# 09_Misc.net
KiCad netlist of a schematic drawn in Altium Designer
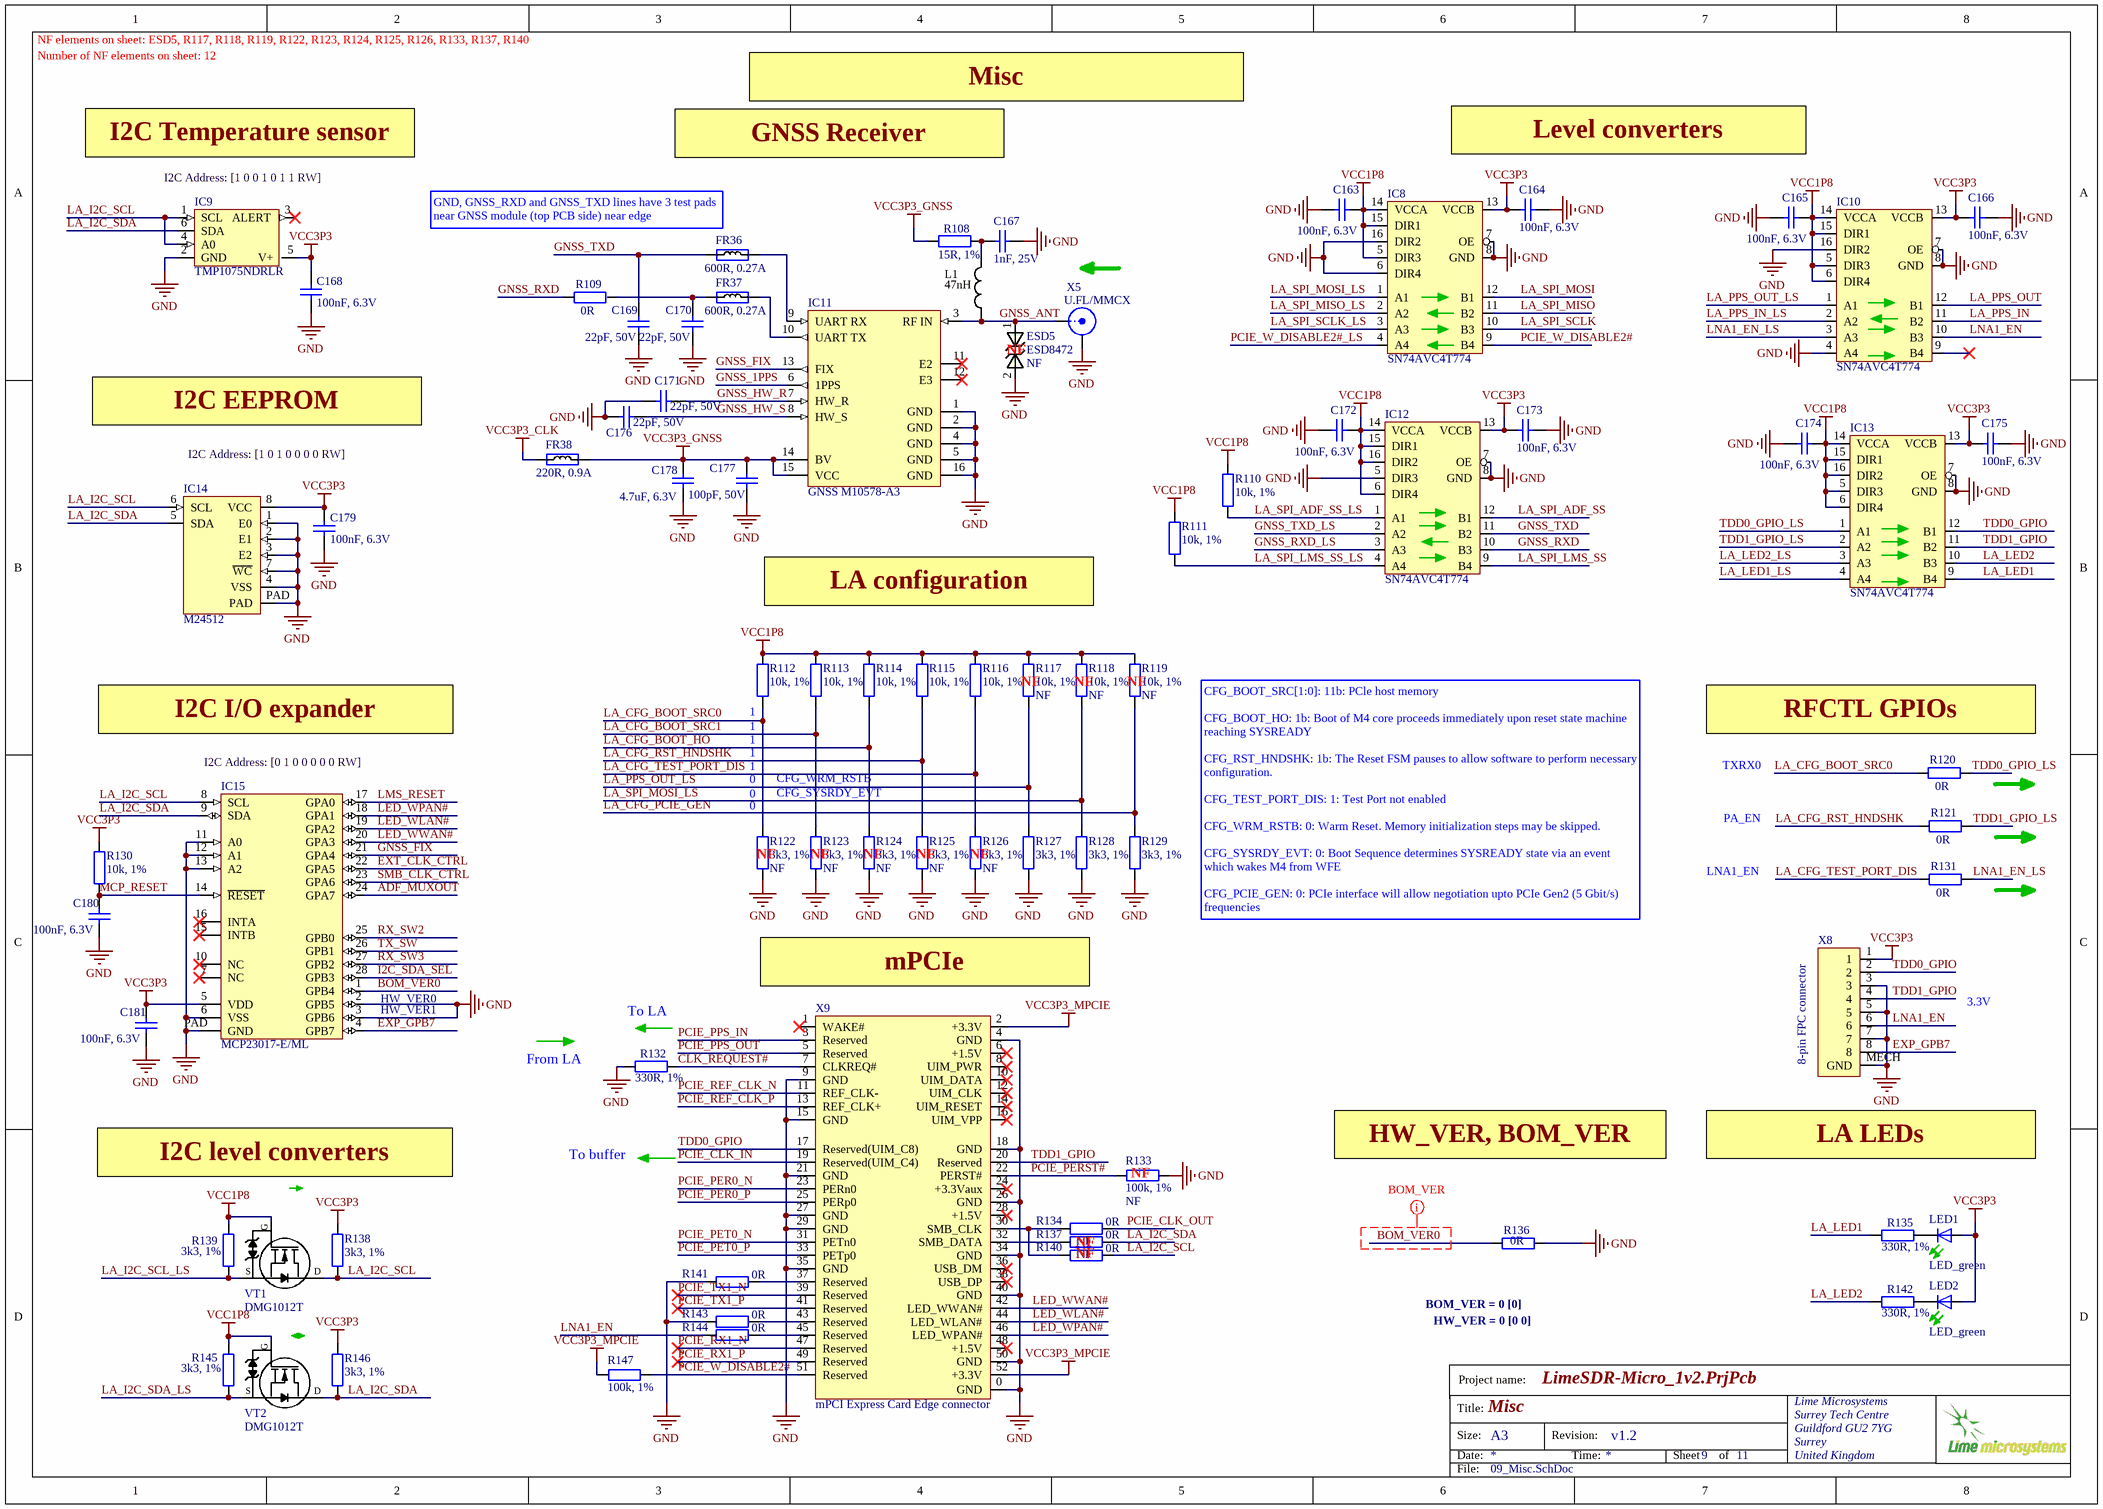
[diagram p0: 09_Misc.SchDoc]

(export (version "E")
  (design (tool "Eeschema 10.0.6"))
  (components
    (comp (ref "C163")
      (value "100nF, 6.3V")
      (footprint "CAP0201")
      (fields (field (name "MANUFACTURER") "Samsung") (field (name "TOLERANCE") "20%"))
      (libsource (lib "LimeMicroAltiumLib_schLib") (part "Cap_0402"))
    )
    (comp (ref "C164")
      (value "100nF, 6.3V")
      (footprint "CAP0201")
      (fields (field (name "MANUFACTURER") "Samsung") (field (name "TOLERANCE") "20%"))
      (libsource (lib "LimeMicroAltiumLib_schLib") (part "Cap_0402"))
    )
    (comp (ref "C165")
      (value "100nF, 6.3V")
      (footprint "CAP0201")
      (fields (field (name "MANUFACTURER") "Samsung") (field (name "TOLERANCE") "20%"))
      (libsource (lib "LimeMicroAltiumLib_schLib") (part "Cap_0402"))
    )
    (comp (ref "C166")
      (value "100nF, 6.3V")
      (footprint "CAP0201")
      (fields (field (name "MANUFACTURER") "Samsung") (field (name "TOLERANCE") "20%"))
      (libsource (lib "LimeMicroAltiumLib_schLib") (part "Cap_0402"))
    )
    (comp (ref "C167")
      (value "1nF, 25V")
      (footprint "CAP0201")
      (fields (field (name "TOLERANCE") "±10%") (field (name "MANUFACTURER") "TDK Corporation"))
      (libsource (lib "LimeMicroAltiumLib_schLib") (part "Cap_0402"))
    )
    (comp (ref "C168")
      (value "100nF, 6.3V")
      (footprint "CAP0201")
      (fields (field (name "MANUFACTURER") "Samsung") (field (name "TOLERANCE") "20%"))
      (libsource (lib "LimeMicroAltiumLib_schLib") (part "Cap_0402"))
    )
    (comp (ref "C169")
      (value "22pF, 50V")
      (footprint "CAP0201")
      (fields
        (field (name "MANUFACTURER") "Murata")
        (field (name "TOLERANCE") "5%")
        (field (name "VOLTAGE") "50V")
      )
      (libsource (lib "LimeMicroAltiumLib_schLib") (part "Cap_0402"))
    )
    (comp (ref "C170")
      (value "22pF, 50V")
      (footprint "CAP0201")
      (fields
        (field (name "MANUFACTURER") "Murata")
        (field (name "TOLERANCE") "5%")
        (field (name "VOLTAGE") "50V")
      )
      (libsource (lib "LimeMicroAltiumLib_schLib") (part "Cap_0402"))
    )
    (comp (ref "C171")
      (value "22pF, 50V")
      (footprint "CAP0201")
      (fields
        (field (name "MANUFACTURER") "Murata")
        (field (name "TOLERANCE") "5%")
        (field (name "VOLTAGE") "50V")
      )
      (libsource (lib "LimeMicroAltiumLib_schLib") (part "Cap_0402"))
    )
    (comp (ref "C172")
      (value "100nF, 6.3V")
      (footprint "CAP0201")
      (fields (field (name "MANUFACTURER") "Samsung") (field (name "TOLERANCE") "20%"))
      (libsource (lib "LimeMicroAltiumLib_schLib") (part "Cap_0402"))
    )
    (comp (ref "C173")
      (value "100nF, 6.3V")
      (footprint "CAP0201")
      (fields (field (name "MANUFACTURER") "Samsung") (field (name "TOLERANCE") "20%"))
      (libsource (lib "LimeMicroAltiumLib_schLib") (part "Cap_0402"))
    )
    (comp (ref "C174")
      (value "100nF, 6.3V")
      (footprint "CAP0201")
      (fields (field (name "MANUFACTURER") "Samsung") (field (name "TOLERANCE") "20%"))
      (libsource (lib "LimeMicroAltiumLib_schLib") (part "Cap_0402"))
    )
    (comp (ref "C175")
      (value "100nF, 6.3V")
      (footprint "CAP0201")
      (fields (field (name "MANUFACTURER") "Samsung") (field (name "TOLERANCE") "20%"))
      (libsource (lib "LimeMicroAltiumLib_schLib") (part "Cap_0402"))
    )
    (comp (ref "C176")
      (value "22pF, 50V")
      (footprint "CAP0201")
      (fields
        (field (name "MANUFACTURER") "Murata")
        (field (name "TOLERANCE") "5%")
        (field (name "VOLTAGE") "50V")
      )
      (libsource (lib "LimeMicroAltiumLib_schLib") (part "Cap_0402"))
    )
    (comp (ref "C177")
      (value "100pF, 50V")
      (footprint "CAP0201")
      (fields
        (field (name "MANUFACTURER") "TDK")
        (field (name "TOLERANCE") "5%")
        (field (name "VOLTAGE") "50V")
      )
      (libsource (lib "LimeMicroAltiumLib_schLib") (part "Cap_0402"))
    )
    (comp (ref "C178")
      (value "4.7uF, 6.3V")
      (footprint "CAP0402")
      (fields
        (field (name "MANUFACTURER") "Murata Electronics North America")
        (field (name "TOLERANCE") "±20%")
      )
      (libsource (lib "LimeMicroAltiumLib_schLib") (part "Cap_0402"))
    )
    (comp (ref "C179")
      (value "100nF, 6.3V")
      (footprint "CAP0201")
      (fields (field (name "MANUFACTURER") "Samsung") (field (name "TOLERANCE") "20%"))
      (libsource (lib "LimeMicroAltiumLib_schLib") (part "Cap_0402"))
    )
    (comp (ref "C180")
      (value "100nF, 6.3V")
      (footprint "CAP0201")
      (fields (field (name "MANUFACTURER") "Samsung") (field (name "TOLERANCE") "20%"))
      (libsource (lib "LimeMicroAltiumLib_schLib") (part "Cap_0402"))
    )
    (comp (ref "C181")
      (value "100nF, 6.3V")
      (footprint "CAP0201")
      (fields (field (name "MANUFACTURER") "Samsung") (field (name "TOLERANCE") "20%"))
      (libsource (lib "LimeMicroAltiumLib_schLib") (part "Cap_0402"))
    )
    (comp (ref "ESD5")
      (value "ESD8472")
      (footprint "ESD8472_X3DFN2")
      (fields (field (name "MANUFACTURER") "ON Semiconductor") (field (name "ASSEMBLY INFO") "NF"))
      (libsource (lib "LimeMicroAltiumLib_schLib") (part "ESD8472"))
    )
    (comp (ref "FR36")
      (value "600R, 0.27A")
      (footprint "RES0201")
      (fields (field (name "MANUFACTURER") "Taiyo Yuden"))
      (libsource (lib "LimeMicroAltiumLib_schLib") (part "Ferrite"))
    )
    (comp (ref "FR37")
      (value "600R, 0.27A")
      (footprint "RES0201")
      (fields (field (name "MANUFACTURER") "Taiyo Yuden"))
      (libsource (lib "LimeMicroAltiumLib_schLib") (part "Ferrite"))
    )
    (comp (ref "FR38")
      (value "220R, 0.9A")
      (footprint "RES0402")
      (fields (field (name "MANUFACTURER") "TDK Corporation"))
      (libsource (lib "LimeFPGAboard_schLib") (part "Ferrite"))
    )
    (comp (ref "IC8")
      (value "SN74AVC4T774")
      (footprint "SN74AVC4T774_v1")
      (fields (field (name "MANUFACTURER") "Texas Instruments"))
      (libsource (lib "LimeMicroAltiumLib") (part "SN74AVC4T774"))
    )
    (comp (ref "IC9")
      (value "TMP1075NDRLR")
      (footprint "TMP1075NDRLR_temperature_sensor_SOT563")
      (fields (field (name "MANUFACTURER") "Texas Instruments"))
      (libsource (lib "LimeMicroAltiumLib_schLib_r04") (part "TMP1075NDRLR_temperature_sensor"))
    )
    (comp (ref "IC10")
      (value "SN74AVC4T774")
      (footprint "SN74AVC4T774_v1")
      (fields (field (name "MANUFACTURER") "Texas Instruments"))
      (libsource (lib "LimeMicroAltiumLib") (part "SN74AVC4T774"))
    )
    (comp (ref "IC11")
      (value "GNSS M10578-A3")
      (footprint "M10578-A3_v2")
      (fields (field (name "MANUFACTURER") "Antenova"))
      (libsource (lib "LimeMicroAltiumLib_schLib_r04") (part "M10578-A3_GPS_GNSS"))
    )
    (comp (ref "IC12")
      (value "SN74AVC4T774")
      (footprint "SN74AVC4T774_v1")
      (fields (field (name "MANUFACTURER") "Texas Instruments"))
      (libsource (lib "LimeMicroAltiumLib") (part "SN74AVC4T774"))
    )
    (comp (ref "IC13")
      (value "SN74AVC4T774")
      (footprint "SN74AVC4T774_v1")
      (fields (field (name "MANUFACTURER") "Texas Instruments"))
      (libsource (lib "LimeMicroAltiumLib") (part "SN74AVC4T774"))
    )
    (comp (ref "IC14")
      (value "M24512")
      (footprint "M24128-DFMC6TG")
      (fields (field (name "MANUFACTURER") "STMicroelectronics"))
      (libsource (lib "LimeMicroAltiumLib_schLib") (part "M24128-DFMC6TG"))
    )
    (comp (ref "IC15")
      (value "MCP23017-E/ML")
      (footprint "MCP23017-E/ML_QFN28")
      (fields (field (name "MANUFACTURER") "Microchip"))
      (libsource (lib "LimeMicroAltiumLib") (part "MCP23017-E/ML_I2C_expander"))
    )
    (comp (ref "L1")
      (value "47nH")
      (footprint "RES0402")
      (fields
        (field (name "MANUFACTURER") "COILCRAFT")
        (field (name "MANUFACTURER PART NUMBER") "0402HP-47NXJLU")
      )
      (libsource (lib "LimeMicroAltiumLib_schLib") (part "Inductor_0603"))
    )
    (comp (ref "LED1")
      (value "LED_green")
      (footprint "LED0201")
      (fields (field (name "MANUFACTURER") "Kingbright"))
      (libsource (lib "LimeFPGAboard_schLib") (part "LED_green"))
    )
    (comp (ref "LED2")
      (value "LED_green")
      (footprint "LED0201")
      (fields (field (name "MANUFACTURER") "Kingbright"))
      (libsource (lib "LimeFPGAboard_schLib") (part "LED_green"))
    )
    (comp (ref "R108")
      (value "15R, 1%")
      (footprint "RES0201")
      (fields (field (name "MANUFACTURER") "Yageo") (field (name "TOLERANCE") "1%"))
      (libsource (lib "LimeFPGAboard_schLib") (part "Res_0402"))
    )
    (comp (ref "R109")
      (value "0R")
      (footprint "RES0201")
      (fields (field (name "MANUFACTURER") "Yageo") (field (name "TOLERANCE") "5%"))
      (libsource (lib "LimeFPGAboard_schLib") (part "Res_0402"))
    )
    (comp (ref "R110")
      (value "10k, 1%")
      (footprint "RES0201")
      (fields (field (name "MANUFACTURER") "Yageo") (field (name "TOLERANCE") "1%"))
      (libsource (lib "LimeFPGAboard_schLib") (part "Res_0402"))
    )
    (comp (ref "R111")
      (value "10k, 1%")
      (footprint "RES0201")
      (fields (field (name "MANUFACTURER") "Yageo") (field (name "TOLERANCE") "1%"))
      (libsource (lib "LimeFPGAboard_schLib") (part "Res_0402"))
    )
    (comp (ref "R112")
      (value "10k, 1%")
      (footprint "RES0201")
      (fields (field (name "MANUFACTURER") "Yageo") (field (name "TOLERANCE") "1%"))
      (libsource (lib "LimeFPGAboard_schLib") (part "Res_0402"))
    )
    (comp (ref "R113")
      (value "10k, 1%")
      (footprint "RES0201")
      (fields (field (name "MANUFACTURER") "Yageo") (field (name "TOLERANCE") "1%"))
      (libsource (lib "LimeFPGAboard_schLib") (part "Res_0402"))
    )
    (comp (ref "R114")
      (value "10k, 1%")
      (footprint "RES0201")
      (fields (field (name "MANUFACTURER") "Yageo") (field (name "TOLERANCE") "1%"))
      (libsource (lib "LimeFPGAboard_schLib") (part "Res_0402"))
    )
    (comp (ref "R115")
      (value "10k, 1%")
      (footprint "RES0201")
      (fields (field (name "MANUFACTURER") "Yageo") (field (name "TOLERANCE") "1%"))
      (libsource (lib "LimeFPGAboard_schLib") (part "Res_0402"))
    )
    (comp (ref "R116")
      (value "10k, 1%")
      (footprint "RES0201")
      (fields (field (name "MANUFACTURER") "Yageo") (field (name "TOLERANCE") "1%"))
      (libsource (lib "LimeFPGAboard_schLib") (part "Res_0402"))
    )
    (comp (ref "R117")
      (value "10k, 1%")
      (footprint "RES0201")
      (fields
        (field (name "ASSEMBLY INFO") "NF")
        (field (name "MANUFACTURER") "Yageo")
        (field (name "TOLERANCE") "1%")
      )
      (libsource (lib "LimeFPGAboard_schLib") (part "Res_0402"))
    )
    (comp (ref "R118")
      (value "10k, 1%")
      (footprint "RES0201")
      (fields
        (field (name "ASSEMBLY INFO") "NF")
        (field (name "MANUFACTURER") "Yageo")
        (field (name "TOLERANCE") "1%")
      )
      (libsource (lib "LimeFPGAboard_schLib") (part "Res_0402"))
    )
    (comp (ref "R119")
      (value "10k, 1%")
      (footprint "RES0201")
      (fields
        (field (name "ASSEMBLY INFO") "NF")
        (field (name "MANUFACTURER") "Yageo")
        (field (name "TOLERANCE") "1%")
      )
      (libsource (lib "LimeFPGAboard_schLib") (part "Res_0402"))
    )
    (comp (ref "R120")
      (value "0R")
      (footprint "RES0201")
      (fields (field (name "MANUFACTURER") "Yageo") (field (name "TOLERANCE") "5%"))
      (libsource (lib "LimeFPGAboard_schLib") (part "Res_0402"))
    )
    (comp (ref "R121")
      (value "0R")
      (footprint "RES0201")
      (fields (field (name "MANUFACTURER") "Yageo") (field (name "TOLERANCE") "5%"))
      (libsource (lib "LimeFPGAboard_schLib") (part "Res_0402"))
    )
    (comp (ref "R122")
      (value "3k3, 1%")
      (footprint "RES0201")
      (fields
        (field (name "ASSEMBLY INFO") "NF")
        (field (name "MANUFACTURER") "Yageo")
        (field (name "TOLERANCE") "1%")
      )
      (libsource (lib "LimeFPGAboard_schLib") (part "Res_0402"))
    )
    (comp (ref "R123")
      (value "3k3, 1%")
      (footprint "RES0201")
      (fields
        (field (name "ASSEMBLY INFO") "NF")
        (field (name "MANUFACTURER") "Yageo")
        (field (name "TOLERANCE") "1%")
      )
      (libsource (lib "LimeFPGAboard_schLib") (part "Res_0402"))
    )
    (comp (ref "R124")
      (value "3k3, 1%")
      (footprint "RES0201")
      (fields
        (field (name "ASSEMBLY INFO") "NF")
        (field (name "MANUFACTURER") "Yageo")
        (field (name "TOLERANCE") "1%")
      )
      (libsource (lib "LimeFPGAboard_schLib") (part "Res_0402"))
    )
    (comp (ref "R125")
      (value "3k3, 1%")
      (footprint "RES0201")
      (fields
        (field (name "ASSEMBLY INFO") "NF")
        (field (name "MANUFACTURER") "Yageo")
        (field (name "TOLERANCE") "1%")
      )
      (libsource (lib "LimeFPGAboard_schLib") (part "Res_0402"))
    )
    (comp (ref "R126")
      (value "3k3, 1%")
      (footprint "RES0201")
      (fields
        (field (name "ASSEMBLY INFO") "NF")
        (field (name "MANUFACTURER") "Yageo")
        (field (name "TOLERANCE") "1%")
      )
      (libsource (lib "LimeFPGAboard_schLib") (part "Res_0402"))
    )
    (comp (ref "R127")
      (value "3k3, 1%")
      (footprint "RES0201")
      (fields (field (name "MANUFACTURER") "Yageo") (field (name "TOLERANCE") "1%"))
      (libsource (lib "LimeFPGAboard_schLib") (part "Res_0402"))
    )
    (comp (ref "R128")
      (value "3k3, 1%")
      (footprint "RES0201")
      (fields (field (name "MANUFACTURER") "Yageo") (field (name "TOLERANCE") "1%"))
      (libsource (lib "LimeFPGAboard_schLib") (part "Res_0402"))
    )
    (comp (ref "R129")
      (value "3k3, 1%")
      (footprint "RES0201")
      (fields (field (name "MANUFACTURER") "Yageo") (field (name "TOLERANCE") "1%"))
      (libsource (lib "LimeFPGAboard_schLib") (part "Res_0402"))
    )
    (comp (ref "R130")
      (value "10k, 1%")
      (footprint "RES0201")
      (fields (field (name "MANUFACTURER") "Yageo") (field (name "TOLERANCE") "1%"))
      (libsource (lib "LimeFPGAboard_schLib") (part "Res_0402"))
    )
    (comp (ref "R131")
      (value "0R")
      (footprint "RES0201")
      (fields (field (name "MANUFACTURER") "Yageo") (field (name "TOLERANCE") "5%"))
      (libsource (lib "LimeFPGAboard_schLib") (part "Res_0402"))
    )
    (comp (ref "R132")
      (value "330R, 1%")
      (footprint "RES0201")
      (fields (field (name "MANUFACTURER") "Vishay Dale") (field (name "TOLERANCE") "1%"))
      (libsource (lib "LimeFPGAboard_schLib") (part "Res_0402"))
    )
    (comp (ref "R133")
      (value "100k, 1%")
      (footprint "RES0201")
      (fields
        (field (name "ASSEMBLY INFO") "NF")
        (field (name "MANUFACTURER") "Yageo")
        (field (name "TOLERANCE") "1%")
      )
      (libsource (lib "LimeMicroAltiumLib_schLib") (part "Res_0402"))
    )
    (comp (ref "R134")
      (value "0R")
      (footprint "RES0201")
      (fields (field (name "MANUFACTURER") "Yageo") (field (name "TOLERANCE") "5%"))
      (libsource (lib "LimeFPGAboard_schLib") (part "Res_0402"))
    )
    (comp (ref "R135")
      (value "330R, 1%")
      (footprint "RES0201")
      (fields (field (name "MANUFACTURER") "Vishay Dale") (field (name "TOLERANCE") "1%"))
      (libsource (lib "LimeFPGAboard_schLib") (part "Res_0402"))
    )
    (comp (ref "R136")
      (value "0R")
      (footprint "RES0201")
      (fields (field (name "MANUFACTURER") "Yageo") (field (name "TOLERANCE") "5%"))
      (libsource (lib "LimeFPGAboard_schLib") (part "Res_0402"))
    )
    (comp (ref "R137")
      (value "0R")
      (footprint "RES0201")
      (fields
        (field (name "ASSEMBLY INFO") "NF")
        (field (name "MANUFACTURER") "Yageo")
        (field (name "TOLERANCE") "5%")
      )
      (libsource (lib "LimeFPGAboard_schLib") (part "Res_0402"))
    )
    (comp (ref "R138")
      (value "3k3, 1%")
      (footprint "RES0201")
      (fields (field (name "MANUFACTURER") "Yageo") (field (name "TOLERANCE") "1%"))
      (libsource (lib "LimeFPGAboard_schLib") (part "Res_0402"))
    )
    (comp (ref "R139")
      (value "3k3, 1%")
      (footprint "RES0201")
      (fields (field (name "MANUFACTURER") "Yageo") (field (name "TOLERANCE") "1%"))
      (libsource (lib "LimeFPGAboard_schLib") (part "Res_0402"))
    )
    (comp (ref "R140")
      (value "0R")
      (footprint "RES0201")
      (fields
        (field (name "ASSEMBLY INFO") "NF")
        (field (name "MANUFACTURER") "Yageo")
        (field (name "TOLERANCE") "5%")
      )
      (libsource (lib "LimeFPGAboard_schLib") (part "Res_0402"))
    )
    (comp (ref "R141")
      (value "0R")
      (footprint "RES0201")
      (fields (field (name "MANUFACTURER") "Yageo") (field (name "TOLERANCE") "5%"))
      (libsource (lib "LimeFPGAboard_schLib") (part "Res_0402"))
    )
    (comp (ref "R142")
      (value "330R, 1%")
      (footprint "RES0201")
      (fields (field (name "MANUFACTURER") "Vishay Dale") (field (name "TOLERANCE") "1%"))
      (libsource (lib "LimeFPGAboard_schLib") (part "Res_0402"))
    )
    (comp (ref "R143")
      (value "0R")
      (footprint "RES0201")
      (fields (field (name "MANUFACTURER") "Yageo") (field (name "TOLERANCE") "5%"))
      (libsource (lib "LimeFPGAboard_schLib") (part "Res_0402"))
    )
    (comp (ref "R144")
      (value "0R")
      (footprint "RES0201")
      (fields (field (name "MANUFACTURER") "Yageo") (field (name "TOLERANCE") "5%"))
      (libsource (lib "LimeFPGAboard_schLib") (part "Res_0402"))
    )
    (comp (ref "R145")
      (value "3k3, 1%")
      (footprint "RES0201")
      (fields (field (name "MANUFACTURER") "Yageo") (field (name "TOLERANCE") "1%"))
      (libsource (lib "LimeFPGAboard_schLib") (part "Res_0402"))
    )
    (comp (ref "R146")
      (value "3k3, 1%")
      (footprint "RES0201")
      (fields (field (name "MANUFACTURER") "Yageo") (field (name "TOLERANCE") "1%"))
      (libsource (lib "LimeFPGAboard_schLib") (part "Res_0402"))
    )
    (comp (ref "R147")
      (value "100k, 1%")
      (footprint "RES0201")
      (fields (field (name "MANUFACTURER") "Yageo") (field (name "TOLERANCE") "1%"))
      (libsource (lib "LimeMicroAltiumLib_schLib") (part "Res_0402"))
    )
    (comp (ref "VT1")
      (value "DMG1012T")
      (footprint "SOT523")
      (fields (field (name "MANUFACTURER") "Diodes Incorporated"))
      (libsource (lib "LimeMicroAltiumLib_schLib_r01") (part "DMG1012T"))
    )
    (comp (ref "VT2")
      (value "DMG1012T")
      (footprint "SOT523")
      (fields (field (name "MANUFACTURER") "Diodes Incorporated"))
      (libsource (lib "LimeMicroAltiumLib_schLib_r01") (part "DMG1012T"))
    )
    (comp (ref "X5")
      (value "U.FL/MMCX")
      (footprint "MMCX_UFL_conn_u_v2")
      (description "CONN UMC RCPT STR 50 OHM SMD")
      (fields (field (name "MANUFACTURER") "Molex, LLC"))
      (libsource (lib "LimeMicroAltiumLib_schLib") (part "RF_IF_connector"))
    )
    (comp (ref "X8")
      (value "8-pin FPC connector")
      (footprint "503480-0800_8PIN_FPC_CONN")
      (fields (field (name "MANUFACTURER") "Molex"))
      (libsource (lib "LimeMicroAltiumLib_schLib_r04") (part "503480-0800_8PIN_FPC_CONN"))
    )
    (comp (ref "X9")
      (value "mPCI Express Card Edge connector")
      (footprint "PCIe_MiniCard")
      (description "PCIe MiniCard full or half size")
      (libsource (lib "LimeMicroAltiumLib_schLib_r04") (part "PCIe_MiniCard_fingers"))
    )
  )
  (nets
    (net (code "1") (name "/ADF_MUXOUT") (class "Default")
      (node (ref "IC15") (pin "24") (pinfunction "GPA7_24") (pintype "bidirectional"))
    )
    (net (code "2") (name "/BOM_VER0") (class "Default")
      (node (ref "IC15") (pin "1") (pinfunction "GPB4_1") (pintype "bidirectional"))
      (node (ref "R136") (pin "1") (pinfunction "1_1") (pintype "passive"))
    )
    (net (code "3") (name "/CLK_REQUEST#") (class "Default")
      (node (ref "R132") (pin "1") (pinfunction "1_1") (pintype "passive"))
      (node (ref "X9") (pin "7") (pinfunction "CLKREQ#_7") (pintype "passive"))
    )
    (net (code "4") (name "/EXP_GPB7") (class "Default")
      (node (ref "IC15") (pin "4") (pinfunction "GPB7_4") (pintype "bidirectional"))
      (node (ref "X8") (pin "8") (pinfunction "8_8") (pintype "passive"))
    )
    (net (code "5") (name "/EXT_CLK_CTRL") (class "Default")
      (node (ref "IC15") (pin "22") (pinfunction "GPA5_22") (pintype "bidirectional"))
    )
    (net (code "6") (name "/GNSS_1PPS") (class "Default")
      (node (ref "IC11") (pin "6") (pinfunction "1PPS_6") (pintype "output"))
    )
    (net (code "7") (name "/GNSS_ANT") (class "Default")
      (node (ref "ESD5") (pin "1") (pinfunction "1_1") (pintype "passive"))
      (node (ref "IC11") (pin "3") (pinfunction "RF_IN_3") (pintype "input"))
      (node (ref "L1") (pin "1") (pinfunction "1_1") (pintype "passive"))
      (node (ref "X5") (pin "1") (pinfunction "X_1") (pintype "passive"))
    )
    (net (code "8") (name "/GNSS_FIX") (class "Default")
      (node (ref "IC11") (pin "13") (pinfunction "FIX_13") (pintype "output"))
      (node (ref "IC15") (pin "21") (pinfunction "GPA4_21") (pintype "bidirectional"))
    )
    (net (code "9") (name "/GNSS_HW_R") (class "Default")
      (node (ref "C171") (pin "1") (pinfunction "1_1") (pintype "passive"))
      (node (ref "IC11") (pin "7") (pinfunction "HW_R_7") (pintype "input"))
    )
    (net (code "10") (name "/GNSS_HW_S") (class "Default")
      (node (ref "C176") (pin "1") (pinfunction "1_1") (pintype "passive"))
      (node (ref "IC11") (pin "8") (pinfunction "HW_S_8") (pintype "input"))
    )
    (net (code "11") (name "/GNSS_RXD") (class "Default")
      (node (ref "IC12") (pin "10") (pinfunction "B3_10") (pintype "passive"))
      (node (ref "R109") (pin "1") (pinfunction "1_1") (pintype "passive"))
    )
    (net (code "12") (name "/GNSS_RXD_LS") (class "Default")
      (node (ref "IC12") (pin "3") (pinfunction "A3_3") (pintype "passive"))
    )
    (net (code "13") (name "/GNSS_TXD") (class "Default")
      (node (ref "C169") (pin "1") (pinfunction "1_1") (pintype "passive"))
      (node (ref "FR36") (pin "1") (pinfunction "1_1") (pintype "passive"))
      (node (ref "IC12") (pin "11") (pinfunction "B2_11") (pintype "passive"))
    )
    (net (code "14") (name "/GNSS_TXD_LS") (class "Default")
      (node (ref "IC12") (pin "2") (pinfunction "A2_2") (pintype "passive"))
    )
    (net (code "15") (name "/I2C_SDA_SEL") (class "Default")
      (node (ref "IC15") (pin "28") (pinfunction "GPB3_28") (pintype "bidirectional"))
    )
    (net (code "16") (name "/LA_CFG_BOOT_HO") (class "Default")
      (node (ref "R114") (pin "2") (pinfunction "2_2") (pintype "passive"))
      (node (ref "R124") (pin "1") (pinfunction "1_1") (pintype "passive"))
    )
    (net (code "17") (name "/LA_CFG_BOOT_SRC0") (class "Default")
      (node (ref "R112") (pin "2") (pinfunction "2_2") (pintype "passive"))
      (node (ref "R120") (pin "1") (pinfunction "1_1") (pintype "passive"))
      (node (ref "R122") (pin "1") (pinfunction "1_1") (pintype "passive"))
    )
    (net (code "18") (name "/LA_CFG_BOOT_SRC1") (class "Default")
      (node (ref "R113") (pin "2") (pinfunction "2_2") (pintype "passive"))
      (node (ref "R123") (pin "1") (pinfunction "1_1") (pintype "passive"))
    )
    (net (code "19") (name "/LA_CFG_PCIE_GEN") (class "Default")
      (node (ref "R119") (pin "2") (pinfunction "2_2") (pintype "passive"))
      (node (ref "R129") (pin "1") (pinfunction "1_1") (pintype "passive"))
    )
    (net (code "20") (name "/LA_CFG_RST_HNDSHK") (class "Default")
      (node (ref "R115") (pin "2") (pinfunction "2_2") (pintype "passive"))
      (node (ref "R121") (pin "1") (pinfunction "1_1") (pintype "passive"))
      (node (ref "R125") (pin "1") (pinfunction "1_1") (pintype "passive"))
    )
    (net (code "21") (name "/LA_CFG_TEST_PORT_DIS") (class "Default")
      (node (ref "R116") (pin "2") (pinfunction "2_2") (pintype "passive"))
      (node (ref "R126") (pin "1") (pinfunction "1_1") (pintype "passive"))
      (node (ref "R131") (pin "1") (pinfunction "1_1") (pintype "passive"))
    )
    (net (code "22") (name "/LA_I2C_SCL") (class "Default")
      (node (ref "IC14") (pin "6") (pinfunction "SCL_6") (pintype "input"))
      (node (ref "IC15") (pin "8") (pinfunction "SCL_8") (pintype "input"))
      (node (ref "IC9") (pin "1") (pinfunction "SCL_1") (pintype "input"))
      (node (ref "IC9") (pin "4") (pinfunction "A0_4") (pintype "input"))
      (node (ref "R138") (pin "2") (pinfunction "2_2") (pintype "passive"))
      (node (ref "R140") (pin "2") (pinfunction "2_2") (pintype "passive"))
      (node (ref "VT1") (pin "D") (pinfunction "D_D") (pintype "passive"))
    )
    (net (code "23") (name "/LA_I2C_SCL_LS") (class "Default")
      (node (ref "R139") (pin "2") (pinfunction "2_2") (pintype "passive"))
      (node (ref "VT1") (pin "S") (pinfunction "S_S") (pintype "passive"))
    )
    (net (code "24") (name "/LA_I2C_SDA") (class "Default")
      (node (ref "IC14") (pin "5") (pinfunction "SDA_5") (pintype "bidirectional"))
      (node (ref "IC15") (pin "9") (pinfunction "SDA_9") (pintype "bidirectional"))
      (node (ref "IC9") (pin "6") (pinfunction "SDA_6") (pintype "bidirectional"))
      (node (ref "R137") (pin "2") (pinfunction "2_2") (pintype "passive"))
      (node (ref "R146") (pin "2") (pinfunction "2_2") (pintype "passive"))
      (node (ref "VT2") (pin "D") (pinfunction "D_D") (pintype "passive"))
    )
    (net (code "25") (name "/LA_I2C_SDA_LS") (class "Default")
      (node (ref "R145") (pin "2") (pinfunction "2_2") (pintype "passive"))
      (node (ref "VT2") (pin "S") (pinfunction "S_S") (pintype "passive"))
    )
    (net (code "26") (name "/LA_LED1") (class "Default")
      (node (ref "IC13") (pin "9") (pinfunction "B4_9") (pintype "passive"))
      (node (ref "R135") (pin "2") (pinfunction "2_2") (pintype "passive"))
    )
    (net (code "27") (name "/LA_LED1_LS") (class "Default")
      (node (ref "IC13") (pin "4") (pinfunction "A4_4") (pintype "passive"))
    )
    (net (code "28") (name "/LA_LED2") (class "Default")
      (node (ref "IC13") (pin "10") (pinfunction "B3_10") (pintype "passive"))
      (node (ref "R142") (pin "2") (pinfunction "2_2") (pintype "passive"))
    )
    (net (code "29") (name "/LA_LED2_LS") (class "Default")
      (node (ref "IC13") (pin "3") (pinfunction "A3_3") (pintype "passive"))
    )
    (net (code "30") (name "/LA_PPS_IN") (class "Default")
      (node (ref "IC10") (pin "11") (pinfunction "B2_11") (pintype "passive"))
    )
    (net (code "31") (name "/LA_PPS_IN_LS") (class "Default")
      (node (ref "IC10") (pin "2") (pinfunction "A2_2") (pintype "passive"))
    )
    (net (code "32") (name "/LA_PPS_OUT") (class "Default")
      (node (ref "IC10") (pin "12") (pinfunction "B1_12") (pintype "passive"))
    )
    (net (code "33") (name "/LA_PPS_OUT_LS") (class "Default")
      (node (ref "IC10") (pin "1") (pinfunction "A1_1") (pintype "passive"))
      (node (ref "R117") (pin "2") (pinfunction "2_2") (pintype "passive"))
      (node (ref "R127") (pin "1") (pinfunction "1_1") (pintype "passive"))
    )
    (net (code "34") (name "/LA_SPI_ADF_SS") (class "Default")
      (node (ref "IC12") (pin "12") (pinfunction "B1_12") (pintype "passive"))
    )
    (net (code "35") (name "/LA_SPI_ADF_SS_LS") (class "Default")
      (node (ref "IC12") (pin "1") (pinfunction "A1_1") (pintype "passive"))
      (node (ref "R110") (pin "2") (pinfunction "2_2") (pintype "passive"))
    )
    (net (code "36") (name "/LA_SPI_LMS_SS") (class "Default")
      (node (ref "IC12") (pin "9") (pinfunction "B4_9") (pintype "passive"))
    )
    (net (code "37") (name "/LA_SPI_LMS_SS_LS") (class "Default")
      (node (ref "IC12") (pin "4") (pinfunction "A4_4") (pintype "passive"))
      (node (ref "R111") (pin "2") (pinfunction "2_2") (pintype "passive"))
    )
    (net (code "38") (name "/LA_SPI_MISO") (class "Default")
      (node (ref "IC8") (pin "11") (pinfunction "B2_11") (pintype "passive"))
    )
    (net (code "39") (name "/LA_SPI_MISO_LS") (class "Default")
      (node (ref "IC8") (pin "2") (pinfunction "A2_2") (pintype "passive"))
    )
    (net (code "40") (name "/LA_SPI_MOSI") (class "Default")
      (node (ref "IC8") (pin "12") (pinfunction "B1_12") (pintype "passive"))
    )
    (net (code "41") (name "/LA_SPI_MOSI_LS") (class "Default")
      (node (ref "IC8") (pin "1") (pinfunction "A1_1") (pintype "passive"))
      (node (ref "R118") (pin "2") (pinfunction "2_2") (pintype "passive"))
      (node (ref "R128") (pin "1") (pinfunction "1_1") (pintype "passive"))
    )
    (net (code "42") (name "/LA_SPI_SCLK") (class "Default")
      (node (ref "IC8") (pin "10") (pinfunction "B3_10") (pintype "passive"))
    )
    (net (code "43") (name "/LA_SPI_SCLK_LS") (class "Default")
      (node (ref "IC8") (pin "3") (pinfunction "A3_3") (pintype "passive"))
    )
    (net (code "44") (name "/LED_WLAN#") (class "Default")
      (node (ref "IC15") (pin "19") (pinfunction "GPA2_19") (pintype "bidirectional"))
      (node (ref "X9") (pin "44") (pinfunction "LED_WLAN#_44") (pintype "passive"))
    )
    (net (code "45") (name "/LED_WPAN#") (class "Default")
      (node (ref "IC15") (pin "18") (pinfunction "GPA1_18") (pintype "bidirectional"))
      (node (ref "X9") (pin "46") (pinfunction "LED_WPAN#_46") (pintype "passive"))
    )
    (net (code "46") (name "/LED_WWAN#") (class "Default")
      (node (ref "IC15") (pin "20") (pinfunction "GPA3_20") (pintype "bidirectional"))
      (node (ref "X9") (pin "42") (pinfunction "LED_WWAN#_42") (pintype "passive"))
    )
    (net (code "47") (name "/LMS_RESET") (class "Default")
      (node (ref "IC15") (pin "17") (pinfunction "GPA0_17") (pintype "bidirectional"))
    )
    (net (code "48") (name "/LNA1_EN") (class "Default")
      (node (ref "IC10") (pin "10") (pinfunction "B3_10") (pintype "passive"))
      (node (ref "R144") (pin "1") (pinfunction "1_1") (pintype "passive"))
      (node (ref "X8") (pin "6") (pinfunction "6_6") (pintype "passive"))
    )
    (net (code "49") (name "/LNA1_EN_LS") (class "Default")
      (node (ref "IC10") (pin "3") (pinfunction "A3_3") (pintype "passive"))
      (node (ref "R131") (pin "2") (pinfunction "2_2") (pintype "passive"))
    )
    (net (code "50") (name "/MCP_RESET") (class "Default")
      (node (ref "C180") (pin "1") (pinfunction "1_1") (pintype "passive"))
      (node (ref "IC15") (pin "14") (pinfunction "~{RESET}_14") (pintype "input"))
      (node (ref "R130") (pin "2") (pinfunction "2_2") (pintype "passive"))
    )
    (net (code "51") (name "/PCIE_CLK_IN") (class "Default")
      (node (ref "X9") (pin "19") (pinfunction "Reserved(UIM_C4)_19") (pintype "passive"))
    )
    (net (code "52") (name "/PCIE_CLK_OUT") (class "Default")
      (node (ref "R134") (pin "2") (pinfunction "2_2") (pintype "passive"))
    )
    (net (code "53") (name "/PCIE_PER0_N") (class "Default")
      (node (ref "X9") (pin "23") (pinfunction "PERn0_23") (pintype "passive"))
    )
    (net (code "54") (name "/PCIE_PER0_P") (class "Default")
      (node (ref "X9") (pin "25") (pinfunction "PERp0_25") (pintype "passive"))
    )
    (net (code "55") (name "/PCIE_PERST#") (class "Default")
      (node (ref "R133") (pin "2") (pinfunction "2_2") (pintype "passive"))
      (node (ref "X9") (pin "22") (pinfunction "PERST#_22") (pintype "passive"))
    )
    (net (code "56") (name "/PCIE_PET0_N") (class "Default")
      (node (ref "X9") (pin "31") (pinfunction "PETn0_31") (pintype "passive"))
    )
    (net (code "57") (name "/PCIE_PET0_P") (class "Default")
      (node (ref "X9") (pin "33") (pinfunction "PETp0_33") (pintype "passive"))
    )
    (net (code "58") (name "/PCIE_PPS_IN") (class "Default")
      (node (ref "X9") (pin "3") (pinfunction "Reserved_3") (pintype "passive"))
    )
    (net (code "59") (name "/PCIE_PPS_OUT") (class "Default")
      (node (ref "X9") (pin "5") (pinfunction "Reserved_5") (pintype "passive"))
    )
    (net (code "60") (name "/PCIE_REF_CLK_N") (class "Default")
      (node (ref "X9") (pin "11") (pinfunction "REF_CLK-_11") (pintype "passive"))
    )
    (net (code "61") (name "/PCIE_REF_CLK_P") (class "Default")
      (node (ref "X9") (pin "13") (pinfunction "REF_CLK+_13") (pintype "passive"))
    )
    (net (code "62") (name "/PCIE_RX1_N") (class "Default")
      (node (ref "X9") (pin "47") (pinfunction "Reserved_47") (pintype "passive+no_connect"))
    )
    (net (code "63") (name "/PCIE_RX1_P") (class "Default")
      (node (ref "X9") (pin "49") (pinfunction "Reserved_49") (pintype "passive+no_connect"))
    )
    (net (code "64") (name "/PCIE_TX1_N") (class "Default")
      (node (ref "X9") (pin "39") (pinfunction "Reserved_39") (pintype "passive+no_connect"))
    )
    (net (code "65") (name "/PCIE_TX1_P") (class "Default")
      (node (ref "X9") (pin "41") (pinfunction "Reserved_41") (pintype "passive+no_connect"))
    )
    (net (code "66") (name "/PCIE_W_DISABLE2#") (class "Default")
      (node (ref "IC8") (pin "9") (pinfunction "B4_9") (pintype "passive"))
      (node (ref "R147") (pin "1") (pinfunction "1_1") (pintype "passive"))
      (node (ref "X9") (pin "51") (pinfunction "Reserved_51") (pintype "passive"))
    )
    (net (code "67") (name "/PCIE_W_DISABLE2#_LS") (class "Default")
      (node (ref "IC8") (pin "4") (pinfunction "A4_4") (pintype "passive"))
    )
    (net (code "68") (name "/RX_SW2") (class "Default")
      (node (ref "IC15") (pin "25") (pinfunction "GPB0_25") (pintype "bidirectional"))
    )
    (net (code "69") (name "/RX_SW3") (class "Default")
      (node (ref "IC15") (pin "27") (pinfunction "GPB2_27") (pintype "bidirectional"))
    )
    (net (code "70") (name "/SMB_CLK_CTRL") (class "Default")
      (node (ref "IC15") (pin "23") (pinfunction "GPA6_23") (pintype "bidirectional"))
    )
    (net (code "71") (name "/TDD0_GPIO") (class "Default")
      (node (ref "IC13") (pin "12") (pinfunction "B1_12") (pintype "passive"))
      (node (ref "X8") (pin "2") (pinfunction "2_2") (pintype "passive"))
      (node (ref "X9") (pin "17") (pinfunction "Reserved(UIM_C8)_17") (pintype "passive"))
    )
    (net (code "72") (name "/TDD0_GPIO_LS") (class "Default")
      (node (ref "IC13") (pin "1") (pinfunction "A1_1") (pintype "passive"))
      (node (ref "R120") (pin "2") (pinfunction "2_2") (pintype "passive"))
    )
    (net (code "73") (name "/TDD1_GPIO") (class "Default")
      (node (ref "IC13") (pin "11") (pinfunction "B2_11") (pintype "passive"))
      (node (ref "X8") (pin "4") (pinfunction "4_4") (pintype "passive"))
      (node (ref "X9") (pin "20") (pinfunction "Reserved_20") (pintype "passive"))
    )
    (net (code "74") (name "/TDD1_GPIO_LS") (class "Default")
      (node (ref "IC13") (pin "2") (pinfunction "A2_2") (pintype "passive"))
      (node (ref "R121") (pin "2") (pinfunction "2_2") (pintype "passive"))
    )
    (net (code "75") (name "/TX_SW") (class "Default")
      (node (ref "IC15") (pin "26") (pinfunction "GPB1_26") (pintype "bidirectional"))
    )
    (net (code "76") (name "GND") (class "Default")
      (node (ref "C163") (pin "1") (pinfunction "1_1") (pintype "passive"))
      (node (ref "C164") (pin "2") (pinfunction "2_2") (pintype "passive"))
      (node (ref "C165") (pin "1") (pinfunction "1_1") (pintype "passive"))
      (node (ref "C166") (pin "2") (pinfunction "2_2") (pintype "passive"))
      (node (ref "C167") (pin "2") (pinfunction "2_2") (pintype "passive"))
      (node (ref "C168") (pin "2") (pinfunction "2_2") (pintype "passive"))
      (node (ref "C169") (pin "2") (pinfunction "2_2") (pintype "passive"))
      (node (ref "C170") (pin "2") (pinfunction "2_2") (pintype "passive"))
      (node (ref "C171") (pin "2") (pinfunction "2_2") (pintype "passive"))
      (node (ref "C172") (pin "1") (pinfunction "1_1") (pintype "passive"))
      (node (ref "C173") (pin "2") (pinfunction "2_2") (pintype "passive"))
      (node (ref "C174") (pin "1") (pinfunction "1_1") (pintype "passive"))
      (node (ref "C175") (pin "2") (pinfunction "2_2") (pintype "passive"))
      (node (ref "C176") (pin "2") (pinfunction "2_2") (pintype "passive"))
      (node (ref "C177") (pin "1") (pinfunction "1_1") (pintype "passive"))
      (node (ref "C178") (pin "1") (pinfunction "1_1") (pintype "passive"))
      (node (ref "C179") (pin "2") (pinfunction "2_2") (pintype "passive"))
      (node (ref "C180") (pin "2") (pinfunction "2_2") (pintype "passive"))
      (node (ref "C181") (pin "2") (pinfunction "2_2") (pintype "passive"))
      (node (ref "ESD5") (pin "2") (pinfunction "2_2") (pintype "passive"))
      (node (ref "IC10") (pin "16") (pinfunction "DIR2_16") (pintype "passive"))
      (node (ref "IC10") (pin "4") (pinfunction "A4_4") (pintype "passive"))
      (node (ref "IC10") (pin "7") (pinfunction "OE_7") (pintype "passive"))
      (node (ref "IC10") (pin "8") (pinfunction "GND_8") (pintype "passive"))
      (node (ref "IC11") (pin "1") (pinfunction "GND_1") (pintype "passive"))
      (node (ref "IC11") (pin "16") (pinfunction "GND_16") (pintype "passive"))
      (node (ref "IC11") (pin "2") (pinfunction "GND_2") (pintype "passive"))
      (node (ref "IC11") (pin "4") (pinfunction "GND_4") (pintype "passive"))
      (node (ref "IC11") (pin "5") (pinfunction "GND_5") (pintype "passive"))
      (node (ref "IC12") (pin "5") (pinfunction "DIR3_5") (pintype "passive"))
      (node (ref "IC12") (pin "7") (pinfunction "OE_7") (pintype "passive"))
      (node (ref "IC12") (pin "8") (pinfunction "GND_8") (pintype "passive"))
      (node (ref "IC13") (pin "7") (pinfunction "OE_7") (pintype "passive"))
      (node (ref "IC13") (pin "8") (pinfunction "GND_8") (pintype "passive"))
      (node (ref "IC14") (pin "1") (pinfunction "E0_1") (pintype "input"))
      (node (ref "IC14") (pin "2") (pinfunction "E1_2") (pintype "input"))
      (node (ref "IC14") (pin "3") (pinfunction "E2_3") (pintype "input"))
      (node (ref "IC14") (pin "4") (pinfunction "VSS_4") (pintype "power_in"))
      (node (ref "IC14") (pin "7") (pinfunction "~{WC}_7") (pintype "input"))
      (node (ref "IC14") (pin "PAD") (pinfunction "PAD_PAD") (pintype "power_in"))
      (node (ref "IC15") (pin "11") (pinfunction "A0_11") (pintype "input"))
      (node (ref "IC15") (pin "12") (pinfunction "A1_12") (pintype "input"))
      (node (ref "IC15") (pin "13") (pinfunction "A2_13") (pintype "input"))
      (node (ref "IC15") (pin "2") (pinfunction "GPB5_2") (pintype "bidirectional"))
      (node (ref "IC15") (pin "3") (pinfunction "GPB6_3") (pintype "bidirectional"))
      (node (ref "IC15") (pin "6") (pinfunction "VSS_6") (pintype "power_in"))
      (node (ref "IC15") (pin "PAD") (pinfunction "GND_PAD") (pintype "passive"))
      (node (ref "IC8") (pin "16") (pinfunction "DIR2_16") (pintype "passive"))
      (node (ref "IC8") (pin "6") (pinfunction "DIR4_6") (pintype "passive"))
      (node (ref "IC8") (pin "7") (pinfunction "OE_7") (pintype "passive"))
      (node (ref "IC8") (pin "8") (pinfunction "GND_8") (pintype "passive"))
      (node (ref "IC9") (pin "2") (pinfunction "GND_2") (pintype "passive"))
      (node (ref "R122") (pin "2") (pinfunction "2_2") (pintype "passive"))
      (node (ref "R123") (pin "2") (pinfunction "2_2") (pintype "passive"))
      (node (ref "R124") (pin "2") (pinfunction "2_2") (pintype "passive"))
      (node (ref "R125") (pin "2") (pinfunction "2_2") (pintype "passive"))
      (node (ref "R126") (pin "2") (pinfunction "2_2") (pintype "passive"))
      (node (ref "R127") (pin "2") (pinfunction "2_2") (pintype "passive"))
      (node (ref "R128") (pin "2") (pinfunction "2_2") (pintype "passive"))
      (node (ref "R129") (pin "2") (pinfunction "2_2") (pintype "passive"))
      (node (ref "R132") (pin "2") (pinfunction "2_2") (pintype "passive"))
      (node (ref "R133") (pin "1") (pinfunction "1_1") (pintype "passive"))
      (node (ref "R136") (pin "2") (pinfunction "2_2") (pintype "passive"))
      (node (ref "R141") (pin "1") (pinfunction "1_1") (pintype "passive"))
      (node (ref "R143") (pin "1") (pinfunction "1_1") (pintype "passive"))
      (node (ref "X5") (pin "2") (pinfunction "Y_2") (pintype "passive"))
      (node (ref "X8") (pin "3") (pinfunction "3_3") (pintype "passive"))
      (node (ref "X8") (pin "5") (pinfunction "5_5") (pintype "passive"))
      (node (ref "X8") (pin "7") (pinfunction "7_7") (pintype "passive"))
      (node (ref "X8") (pin "MECH") (pinfunction "GND_MECH") (pintype "passive"))
      (node (ref "X9") (pin "0") (pinfunction "GND_0") (pintype "passive"))
      (node (ref "X9") (pin "15") (pinfunction "GND_15") (pintype "passive"))
      (node (ref "X9") (pin "18") (pinfunction "GND_18") (pintype "passive"))
      (node (ref "X9") (pin "21") (pinfunction "GND_21") (pintype "passive"))
      (node (ref "X9") (pin "26") (pinfunction "GND_26") (pintype "passive"))
      (node (ref "X9") (pin "27") (pinfunction "GND_27") (pintype "passive"))
      (node (ref "X9") (pin "29") (pinfunction "GND_29") (pintype "passive"))
      (node (ref "X9") (pin "34") (pinfunction "GND_34") (pintype "passive"))
      (node (ref "X9") (pin "35") (pinfunction "GND_35") (pintype "passive"))
      (node (ref "X9") (pin "4") (pinfunction "GND_4") (pintype "passive"))
      (node (ref "X9") (pin "40") (pinfunction "GND_40") (pintype "passive"))
      (node (ref "X9") (pin "50") (pinfunction "GND_50") (pintype "passive"))
      (node (ref "X9") (pin "9") (pinfunction "GND_9") (pintype "passive"))
    )
    (net (code "77") (name "Net-(C167-Pad1)") (class "Default")
      (node (ref "C167") (pin "1") (pinfunction "1_1") (pintype "passive"))
      (node (ref "L1") (pin "2") (pinfunction "2_2") (pintype "passive"))
      (node (ref "R108") (pin "1") (pinfunction "1_1") (pintype "passive"))
    )
    (net (code "78") (name "Net-(C170-Pad1)") (class "Default")
      (node (ref "C170") (pin "1") (pinfunction "1_1") (pintype "passive"))
      (node (ref "FR37") (pin "1") (pinfunction "1_1") (pintype "passive"))
      (node (ref "R109") (pin "2") (pinfunction "2_2") (pintype "passive"))
    )
    (net (code "79") (name "Net-(IC11-UART_RX)") (class "Default")
      (node (ref "FR36") (pin "2") (pinfunction "2_2") (pintype "passive"))
      (node (ref "IC11") (pin "9") (pinfunction "UART_RX_9") (pintype "input"))
    )
    (net (code "80") (name "Net-(IC11-UART_TX)") (class "Default")
      (node (ref "FR37") (pin "2") (pinfunction "2_2") (pintype "passive"))
      (node (ref "IC11") (pin "10") (pinfunction "UART_TX_10") (pintype "output"))
    )
    (net (code "81") (name "Net-(LED1-C)") (class "Default")
      (node (ref "LED1") (pin "K") (pinfunction "C_K") (pintype "power_in"))
      (node (ref "R135") (pin "1") (pinfunction "1_1") (pintype "passive"))
    )
    (net (code "82") (name "Net-(LED2-C)") (class "Default")
      (node (ref "LED2") (pin "K") (pinfunction "C_K") (pintype "power_in"))
      (node (ref "R142") (pin "1") (pinfunction "1_1") (pintype "passive"))
    )
    (net (code "83") (name "Net-(R141-Pad2)") (class "Default")
      (node (ref "R141") (pin "2") (pinfunction "2_2") (pintype "passive"))
      (node (ref "X9") (pin "37") (pinfunction "Reserved_37") (pintype "passive"))
    )
    (net (code "84") (name "Net-(R143-Pad2)") (class "Default")
      (node (ref "R143") (pin "2") (pinfunction "2_2") (pintype "passive"))
      (node (ref "X9") (pin "43") (pinfunction "Reserved_43") (pintype "passive"))
    )
    (net (code "85") (name "Net-(R144-Pad2)") (class "Default")
      (node (ref "R144") (pin "2") (pinfunction "2_2") (pintype "passive"))
      (node (ref "X9") (pin "45") (pinfunction "Reserved_45") (pintype "passive"))
    )
    (net (code "86") (name "Net-(X9-SMB_CLK)") (class "Default")
      (node (ref "R134") (pin "1") (pinfunction "1_1") (pintype "passive"))
      (node (ref "R140") (pin "1") (pinfunction "1_1") (pintype "passive"))
      (node (ref "X9") (pin "30") (pinfunction "SMB_CLK_30") (pintype "passive"))
    )
    (net (code "87") (name "Net-(X9-SMB_DATA)") (class "Default")
      (node (ref "R137") (pin "1") (pinfunction "1_1") (pintype "passive"))
      (node (ref "X9") (pin "32") (pinfunction "SMB_DATA_32") (pintype "passive"))
    )
    (net (code "88") (name "VCC1P8") (class "Default")
      (node (ref "C163") (pin "2") (pinfunction "2_2") (pintype "passive"))
      (node (ref "C165") (pin "2") (pinfunction "2_2") (pintype "passive"))
      (node (ref "C172") (pin "2") (pinfunction "2_2") (pintype "passive"))
      (node (ref "C174") (pin "2") (pinfunction "2_2") (pintype "passive"))
      (node (ref "IC10") (pin "14") (pinfunction "VCCA_14") (pintype "passive"))
      (node (ref "IC10") (pin "15") (pinfunction "DIR1_15") (pintype "passive"))
      (node (ref "IC10") (pin "5") (pinfunction "DIR3_5") (pintype "passive"))
      (node (ref "IC10") (pin "6") (pinfunction "DIR4_6") (pintype "passive"))
      (node (ref "IC12") (pin "14") (pinfunction "VCCA_14") (pintype "passive"))
      (node (ref "IC12") (pin "15") (pinfunction "DIR1_15") (pintype "passive"))
      (node (ref "IC12") (pin "16") (pinfunction "DIR2_16") (pintype "passive"))
      (node (ref "IC12") (pin "6") (pinfunction "DIR4_6") (pintype "passive"))
      (node (ref "IC13") (pin "14") (pinfunction "VCCA_14") (pintype "passive"))
      (node (ref "IC13") (pin "15") (pinfunction "DIR1_15") (pintype "passive"))
      (node (ref "IC13") (pin "16") (pinfunction "DIR2_16") (pintype "passive"))
      (node (ref "IC13") (pin "5") (pinfunction "DIR3_5") (pintype "passive"))
      (node (ref "IC13") (pin "6") (pinfunction "DIR4_6") (pintype "passive"))
      (node (ref "IC8") (pin "14") (pinfunction "VCCA_14") (pintype "passive"))
      (node (ref "IC8") (pin "15") (pinfunction "DIR1_15") (pintype "passive"))
      (node (ref "IC8") (pin "5") (pinfunction "DIR3_5") (pintype "passive"))
      (node (ref "R110") (pin "1") (pinfunction "1_1") (pintype "passive"))
      (node (ref "R111") (pin "1") (pinfunction "1_1") (pintype "passive"))
      (node (ref "R112") (pin "1") (pinfunction "1_1") (pintype "passive"))
      (node (ref "R113") (pin "1") (pinfunction "1_1") (pintype "passive"))
      (node (ref "R114") (pin "1") (pinfunction "1_1") (pintype "passive"))
      (node (ref "R115") (pin "1") (pinfunction "1_1") (pintype "passive"))
      (node (ref "R116") (pin "1") (pinfunction "1_1") (pintype "passive"))
      (node (ref "R117") (pin "1") (pinfunction "1_1") (pintype "passive"))
      (node (ref "R118") (pin "1") (pinfunction "1_1") (pintype "passive"))
      (node (ref "R119") (pin "1") (pinfunction "1_1") (pintype "passive"))
      (node (ref "R139") (pin "1") (pinfunction "1_1") (pintype "passive"))
      (node (ref "R145") (pin "1") (pinfunction "1_1") (pintype "passive"))
      (node (ref "VT1") (pin "G") (pinfunction "G_G") (pintype "passive"))
      (node (ref "VT2") (pin "G") (pinfunction "G_G") (pintype "passive"))
    )
    (net (code "89") (name "VCC3P3") (class "Default")
      (node (ref "C164") (pin "1") (pinfunction "1_1") (pintype "passive"))
      (node (ref "C166") (pin "1") (pinfunction "1_1") (pintype "passive"))
      (node (ref "C168") (pin "1") (pinfunction "1_1") (pintype "passive"))
      (node (ref "C173") (pin "1") (pinfunction "1_1") (pintype "passive"))
      (node (ref "C175") (pin "1") (pinfunction "1_1") (pintype "passive"))
      (node (ref "C179") (pin "1") (pinfunction "1_1") (pintype "passive"))
      (node (ref "C181") (pin "1") (pinfunction "1_1") (pintype "passive"))
      (node (ref "IC10") (pin "13") (pinfunction "VCCB_13") (pintype "passive"))
      (node (ref "IC12") (pin "13") (pinfunction "VCCB_13") (pintype "passive"))
      (node (ref "IC13") (pin "13") (pinfunction "VCCB_13") (pintype "passive"))
      (node (ref "IC14") (pin "8") (pinfunction "VCC_8") (pintype "power_in"))
      (node (ref "IC15") (pin "5") (pinfunction "VDD_5") (pintype "power_in"))
      (node (ref "IC8") (pin "13") (pinfunction "VCCB_13") (pintype "passive"))
      (node (ref "IC9") (pin "5") (pinfunction "V+_5") (pintype "power_in"))
      (node (ref "LED1") (pin "A") (pinfunction "A_A") (pintype "power_in"))
      (node (ref "LED2") (pin "A") (pinfunction "A_A") (pintype "power_in"))
      (node (ref "R130") (pin "1") (pinfunction "1_1") (pintype "passive"))
      (node (ref "R138") (pin "1") (pinfunction "1_1") (pintype "passive"))
      (node (ref "R146") (pin "1") (pinfunction "1_1") (pintype "passive"))
      (node (ref "X8") (pin "1") (pinfunction "1_1") (pintype "passive"))
    )
    (net (code "90") (name "VCC3P3_CLK") (class "Default")
      (node (ref "FR38") (pin "1") (pinfunction "1_1") (pintype "passive"))
    )
    (net (code "91") (name "VCC3P3_GNSS") (class "Default")
      (node (ref "C177") (pin "2") (pinfunction "2_2") (pintype "passive"))
      (node (ref "C178") (pin "2") (pinfunction "2_2") (pintype "passive"))
      (node (ref "FR38") (pin "2") (pinfunction "2_2") (pintype "passive"))
      (node (ref "IC11") (pin "14") (pinfunction "BV_14") (pintype "power_in"))
      (node (ref "IC11") (pin "15") (pinfunction "VCC_15") (pintype "power_in"))
      (node (ref "R108") (pin "2") (pinfunction "2_2") (pintype "passive"))
    )
    (net (code "92") (name "VCC3P3_MPCIE") (class "Default")
      (node (ref "R147") (pin "2") (pinfunction "2_2") (pintype "passive"))
      (node (ref "X9") (pin "2") (pinfunction "+3.3V_2") (pintype "passive"))
      (node (ref "X9") (pin "52") (pinfunction "+3.3V_52") (pintype "passive"))
    )
    (net (code "93") (name "unconnected-(IC9-ALERT-Pad3)") (class "Default")
      (node (ref "IC9") (pin "3") (pinfunction "ALERT_3") (pintype "output+no_connect"))
    )
    (net (code "94") (name "unconnected-(IC10-B4-Pad9)") (class "Default")
      (node (ref "IC10") (pin "9") (pinfunction "B4_9") (pintype "passive+no_connect"))
    )
    (net (code "95") (name "unconnected-(IC11-E2-Pad11)") (class "Default")
      (node (ref "IC11") (pin "11") (pinfunction "E2_11") (pintype "passive+no_connect"))
    )
    (net (code "96") (name "unconnected-(IC11-E3-Pad12)") (class "Default")
      (node (ref "IC11") (pin "12") (pinfunction "E3_12") (pintype "passive+no_connect"))
    )
    (net (code "97") (name "unconnected-(IC15-INTA-Pad16)") (class "Default")
      (node (ref "IC15") (pin "16") (pinfunction "INTA_16") (pintype "open_collector+no_connect"))
    )
    (net (code "98") (name "unconnected-(IC15-INTB-Pad15)") (class "Default")
      (node (ref "IC15") (pin "15") (pinfunction "INTB_15") (pintype "open_collector+no_connect"))
    )
    (net (code "99") (name "unconnected-(IC15-NC-Pad7)") (class "Default")
      (node (ref "IC15") (pin "7") (pinfunction "NC_7") (pintype "passive+no_connect"))
    )
    (net (code "100") (name "unconnected-(IC15-NC-Pad10)") (class "Default")
      (node (ref "IC15") (pin "10") (pinfunction "NC_10") (pintype "passive+no_connect"))
    )
    (net (code "101") (name "unconnected-(X9-+1.5V-Pad6)") (class "Default")
      (node (ref "X9") (pin "6") (pinfunction "+1.5V_6") (pintype "passive+no_connect"))
    )
    (net (code "102") (name "unconnected-(X9-+1.5V-Pad28)") (class "Default")
      (node (ref "X9") (pin "28") (pinfunction "+1.5V_28") (pintype "passive+no_connect"))
    )
    (net (code "103") (name "unconnected-(X9-+1.5V-Pad48)") (class "Default")
      (node (ref "X9") (pin "48") (pinfunction "+1.5V_48") (pintype "passive+no_connect"))
    )
    (net (code "104") (name "unconnected-(X9-+3.3Vaux-Pad24)") (class "Default")
      (node (ref "X9") (pin "24") (pinfunction "+3.3Vaux_24") (pintype "passive+no_connect"))
    )
    (net (code "105") (name "unconnected-(X9-UIM_CLK-Pad12)") (class "Default")
      (node (ref "X9") (pin "12") (pinfunction "UIM_CLK_12") (pintype "passive+no_connect"))
    )
    (net (code "106") (name "unconnected-(X9-UIM_DATA-Pad10)") (class "Default")
      (node (ref "X9") (pin "10") (pinfunction "UIM_DATA_10") (pintype "passive+no_connect"))
    )
    (net (code "107") (name "unconnected-(X9-UIM_PWR-Pad8)") (class "Default")
      (node (ref "X9") (pin "8") (pinfunction "UIM_PWR_8") (pintype "passive+no_connect"))
    )
    (net (code "108") (name "unconnected-(X9-UIM_RESET-Pad14)") (class "Default")
      (node (ref "X9") (pin "14") (pinfunction "UIM_RESET_14") (pintype "passive+no_connect"))
    )
    (net (code "109") (name "unconnected-(X9-UIM_VPP-Pad16)") (class "Default")
      (node (ref "X9") (pin "16") (pinfunction "UIM_VPP_16") (pintype "passive+no_connect"))
    )
    (net (code "110") (name "unconnected-(X9-USB_DM-Pad36)") (class "Default")
      (node (ref "X9") (pin "36") (pinfunction "USB_DM_36") (pintype "passive+no_connect"))
    )
    (net (code "111") (name "unconnected-(X9-USB_DP-Pad38)") (class "Default")
      (node (ref "X9") (pin "38") (pinfunction "USB_DP_38") (pintype "passive+no_connect"))
    )
    (net (code "112") (name "unconnected-(X9-WAKE#-Pad1)") (class "Default")
      (node (ref "X9") (pin "1") (pinfunction "WAKE#_1") (pintype "passive+no_connect"))
    )
  )
)
